# FTDI_ISP.net
KiCad netlist of a schematic drawn in Altium Designer
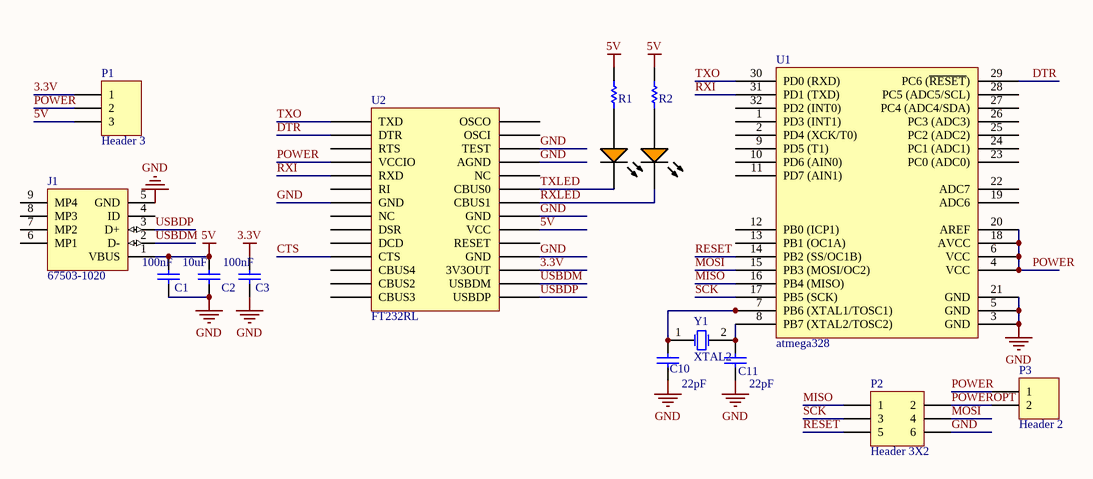
[diagram p0: FTDI_ISP.SchDoc]

(export (version "E")
  (design (tool "Eeschema 10.0.6"))
  (components
    (comp (ref "C1")
      (value "100nF")
      (footprint "CAPC0603(1608)100_N")
      (description "CAP 100nF 10V -20% to +80% 0603 (1608 Metric) Thickness 1mm SMD")
      (fields (field (name "TOLERANCE") "-20% to +80%"))
      (libsource (lib "Altium Content Vault") (part "CMP-1035-02582-1"))
    )
    (comp (ref "C2")
      (value "10uF")
      (footprint "CAPC0603(1608)100_N")
      (description "CAP 10uF 10V ±10% 0603 (1608 Metric) Thickness 1mm SMD")
      (fields (field (name "TOLERANCE") "±10%"))
      (libsource (lib "Altium Content Vault") (part "CMP-1035-02799-1"))
    )
    (comp (ref "C3")
      (value "100nF")
      (footprint "CAPC0603(1608)100_N")
      (description "CAP 100nF 10V -20% to +80% 0603 (1608 Metric) Thickness 1mm SMD")
      (fields (field (name "TOLERANCE") "-20% to +80%"))
      (libsource (lib "Altium Content Vault") (part "CMP-1035-02582-1"))
    )
    (comp (ref "C10")
      (value "22pF")
      (footprint "CAPC0603(1608)100_M")
      (description "CAP 22pF 10V ±0.25pF 0603 (1608 Metric) Thickness 1mm SMD")
      (fields (field (name "TOLERANCE") "±0.25pF"))
      (libsource (lib "Altium Content Vault") (part "CMP-1035-00797-1"))
    )
    (comp (ref "C11")
      (value "22pF")
      (footprint "CAPC0603(1608)100_M")
      (description "CAP 22pF 10V ±0.25pF 0603 (1608 Metric) Thickness 1mm SMD")
      (fields (field (name "TOLERANCE") "±0.25pF"))
      (libsource (lib "Altium Content Vault") (part "CMP-1035-00797-1"))
    )
    (comp (ref "D1")
      (value "APG1608SEKC/T")
      (footprint "KING-LED0603-25-ORANGE_V")
      (description "LED, SMT, 0603(1608), 0.25mm Tthickness, Super Bright Orange")
      (libsource (lib "Altium Content Vault") (part "CMP-0239-00002-1"))
    )
    (comp (ref "D2")
      (value "APG1608SEKC/T")
      (footprint "KING-LED0603-25-ORANGE_V")
      (description "LED, SMT, 0603(1608), 0.25mm Tthickness, Super Bright Orange")
      (libsource (lib "Altium Content Vault") (part "CMP-0239-00002-1"))
    )
    (comp (ref "J1")
      (value "67503-1020")
      (footprint "MOLX-67503-1020_V")
      (description "USB, MINI, SMD, RA KME04-USBMU03A01")
      (fields (field (name "MANUFACTURER") "Molex"))
      (libsource (lib "Altium Content Vault") (part "CMP-0411-00002-1"))
    )
    (comp (ref "P1")
      (value "Header 3")
      (footprint "HDR1X3")
      (description "Header, 3-Pin")
      (fields (field (name "PUBLISHER") "Altium Limited"))
      (libsource (lib "Miscellaneous Connectors") (part "Header 3"))
    )
    (comp (ref "P2")
      (value "Header 3X2")
      (footprint "HDR2X3")
      (description "Header, 3-Pin, Dual row")
      (fields (field (name "PUBLISHER") "Altium Limited"))
      (libsource (lib "Miscellaneous Connectors") (part "Header 3X2"))
    )
    (comp (ref "P3")
      (value "Header 2")
      (footprint "HDR1X2")
      (description "Header, 2-Pin")
      (fields (field (name "PUBLISHER") "Altium Limited"))
      (libsource (lib "Miscellaneous Connectors") (part "Header 2"))
    )
    (comp (ref "R1")
      (value "1K1 5% 0603(1608)")
      (footprint "RESC0603(1608)_N")
      (description "1K1 0.1W 5% 0603 (1608 Metric)  SMD")
      (fields (field (name "POWER") "0.1 W") (field (name "TOLERANCE") "5 %"))
      (libsource (lib "Altium Content Vault") (part "CMP-1012-00075-1"))
    )
    (comp (ref "R2")
      (value "1K1 5% 0603(1608)")
      (footprint "RESC0603(1608)_N")
      (description "1K1 0.1W 5% 0603 (1608 Metric)  SMD")
      (fields (field (name "POWER") "0.1 W") (field (name "TOLERANCE") "5 %"))
      (libsource (lib "Altium Content Vault") (part "CMP-1012-00075-1"))
    )
    (comp (ref "U1")
      (value "atmega328")
      (footprint "atmega44/88/168")
      (libsource (lib "Integrated_Library") (part "atmega88"))
    )
    (comp (ref "U2")
      (value "FT232RL")
      (footprint "FT232RL-SOP")
      (libsource (lib "Integrated_Library") (part "FT232RL"))
    )
    (comp (ref "Y1")
      (value "XTAL2")
      (footprint "HC49/US")
      (description "Two Lead Crystal Oscillator")
      (libsource (lib "Integrated_Library") (part "XTAL2"))
    )
  )
  (nets
    (net (code "1") (name "/CTS") (class "Default")
      (node (ref "U2") (pin "11") (pinfunction "CTS_11") (pintype "passive"))
    )
    (net (code "2") (name "/DTR") (class "Default")
      (node (ref "U1") (pin "29") (pinfunction "PC6_(~{RESET})_29") (pintype "passive"))
      (node (ref "U2") (pin "2") (pinfunction "DTR_2") (pintype "passive"))
    )
    (net (code "3") (name "/MISO") (class "Default")
      (node (ref "P2") (pin "1") (pinfunction "1_1") (pintype "passive"))
      (node (ref "U1") (pin "16") (pinfunction "PB4_(MISO)_16") (pintype "passive"))
    )
    (net (code "4") (name "/MOSI") (class "Default")
      (node (ref "P2") (pin "4") (pinfunction "4_4") (pintype "passive"))
      (node (ref "U1") (pin "15") (pinfunction "PB3_(MOSI/OC2)_15") (pintype "passive"))
    )
    (net (code "5") (name "/POWER") (class "Default")
      (node (ref "P1") (pin "2") (pinfunction "2_2") (pintype "passive"))
      (node (ref "P3") (pin "1") (pinfunction "1_1") (pintype "passive"))
      (node (ref "U1") (pin "18") (pinfunction "AVCC_18") (pintype "passive"))
      (node (ref "U1") (pin "20") (pinfunction "AREF_20") (pintype "passive"))
      (node (ref "U1") (pin "4") (pinfunction "VCC_4") (pintype "passive"))
      (node (ref "U1") (pin "6") (pinfunction "VCC_6") (pintype "passive"))
      (node (ref "U2") (pin "4") (pinfunction "VCCIO_4") (pintype "passive"))
    )
    (net (code "6") (name "/POWEROPT") (class "Default")
      (node (ref "P2") (pin "2") (pinfunction "2_2") (pintype "passive"))
      (node (ref "P3") (pin "2") (pinfunction "2_2") (pintype "passive"))
    )
    (net (code "7") (name "/RESET") (class "Default")
      (node (ref "P2") (pin "5") (pinfunction "5_5") (pintype "passive"))
      (node (ref "U1") (pin "14") (pinfunction "PB2_(SS/OC1B)_14") (pintype "passive"))
    )
    (net (code "8") (name "/RXI") (class "Default")
      (node (ref "U1") (pin "31") (pinfunction "PD1_(TXD)_31") (pintype "passive"))
      (node (ref "U2") (pin "5") (pinfunction "RXD_5") (pintype "passive"))
    )
    (net (code "9") (name "/RXLED") (class "Default")
      (node (ref "D2") (pin "2") (pinfunction "K_2") (pintype "passive"))
      (node (ref "U2") (pin "22") (pinfunction "CBUS1_22") (pintype "passive"))
    )
    (net (code "10") (name "/SCK") (class "Default")
      (node (ref "P2") (pin "3") (pinfunction "3_3") (pintype "passive"))
      (node (ref "U1") (pin "17") (pinfunction "PB5_(SCK)_17") (pintype "passive"))
    )
    (net (code "11") (name "/TXLED") (class "Default")
      (node (ref "D1") (pin "2") (pinfunction "K_2") (pintype "passive"))
      (node (ref "U2") (pin "23") (pinfunction "CBUS0_23") (pintype "passive"))
    )
    (net (code "12") (name "/TXO") (class "Default")
      (node (ref "U1") (pin "30") (pinfunction "PD0_(RXD)_30") (pintype "passive"))
      (node (ref "U2") (pin "1") (pinfunction "TXD_1") (pintype "passive"))
    )
    (net (code "13") (name "/USBDM") (class "Default")
      (node (ref "J1") (pin "2") (pinfunction "D-_2") (pintype "bidirectional"))
      (node (ref "U2") (pin "16") (pinfunction "USBDM_16") (pintype "passive"))
    )
    (net (code "14") (name "/USBDP") (class "Default")
      (node (ref "J1") (pin "3") (pinfunction "D+_3") (pintype "bidirectional"))
      (node (ref "U2") (pin "15") (pinfunction "USBDP_15") (pintype "passive"))
    )
    (net (code "15") (name "3.3V") (class "Default")
      (node (ref "C3") (pin "2") (pinfunction "2_2") (pintype "passive"))
      (node (ref "P1") (pin "1") (pinfunction "1_1") (pintype "passive"))
      (node (ref "U2") (pin "17") (pinfunction "3V3OUT_17") (pintype "passive"))
    )
    (net (code "16") (name "5V") (class "Default")
      (node (ref "C1") (pin "2") (pinfunction "2_2") (pintype "passive"))
      (node (ref "C2") (pin "2") (pinfunction "2_2") (pintype "passive"))
      (node (ref "J1") (pin "1") (pinfunction "VBUS_1") (pintype "power_in"))
      (node (ref "P1") (pin "3") (pinfunction "3_3") (pintype "passive"))
      (node (ref "R1") (pin "1") (pinfunction "1_1") (pintype "passive"))
      (node (ref "R2") (pin "1") (pinfunction "1_1") (pintype "passive"))
      (node (ref "U2") (pin "20") (pinfunction "VCC_20") (pintype "passive"))
    )
    (net (code "17") (name "GND") (class "Default")
      (node (ref "C1") (pin "1") (pinfunction "1_1") (pintype "passive"))
      (node (ref "C10") (pin "1") (pinfunction "1_1") (pintype "passive"))
      (node (ref "C11") (pin "1") (pinfunction "1_1") (pintype "passive"))
      (node (ref "C2") (pin "1") (pinfunction "1_1") (pintype "passive"))
      (node (ref "C3") (pin "1") (pinfunction "1_1") (pintype "passive"))
      (node (ref "J1") (pin "5") (pinfunction "GND_5") (pintype "power_in"))
      (node (ref "P2") (pin "6") (pinfunction "6_6") (pintype "passive"))
      (node (ref "U1") (pin "21") (pinfunction "GND_21") (pintype "passive"))
      (node (ref "U1") (pin "3") (pinfunction "GND_3") (pintype "passive"))
      (node (ref "U1") (pin "5") (pinfunction "GND_5") (pintype "passive"))
      (node (ref "U2") (pin "18") (pinfunction "GND_18") (pintype "passive"))
      (node (ref "U2") (pin "21") (pinfunction "GND_21") (pintype "passive"))
      (node (ref "U2") (pin "25") (pinfunction "AGND_25") (pintype "passive"))
      (node (ref "U2") (pin "26") (pinfunction "TEST_26") (pintype "passive"))
      (node (ref "U2") (pin "7") (pinfunction "GND_7") (pintype "passive"))
    )
    (net (code "18") (name "Net-(D1-A)") (class "Default")
      (node (ref "D1") (pin "1") (pinfunction "A_1") (pintype "passive"))
      (node (ref "R1") (pin "2") (pinfunction "2_2") (pintype "passive"))
    )
    (net (code "19") (name "Net-(D2-A)") (class "Default")
      (node (ref "D2") (pin "1") (pinfunction "A_1") (pintype "passive"))
      (node (ref "R2") (pin "2") (pinfunction "2_2") (pintype "passive"))
    )
    (net (code "20") (name "Net-(U1-PB6_(XTAL1{slash}TOSC1))") (class "Default")
      (node (ref "C10") (pin "2") (pinfunction "2_2") (pintype "passive"))
      (node (ref "U1") (pin "7") (pinfunction "PB6_(XTAL1/TOSC1)_7") (pintype "passive"))
      (node (ref "Y1") (pin "1") (pinfunction "OSC1_1") (pintype "passive"))
    )
    (net (code "21") (name "Net-(U1-PB7_(XTAL2{slash}TOSC2))") (class "Default")
      (node (ref "C11") (pin "2") (pinfunction "2_2") (pintype "passive"))
      (node (ref "U1") (pin "8") (pinfunction "PB7_(XTAL2/TOSC2)_8") (pintype "passive"))
      (node (ref "Y1") (pin "2") (pinfunction "OSC2_2") (pintype "passive"))
    )
    (net (code "22") (name "unconnected-(J1-ID-Pad4)") (class "Default")
      (node (ref "J1") (pin "4") (pinfunction "ID_4") (pintype "passive"))
    )
    (net (code "23") (name "unconnected-(J1-MP1-Pad6)") (class "Default")
      (node (ref "J1") (pin "6") (pinfunction "MP1_6") (pintype "passive"))
    )
    (net (code "24") (name "unconnected-(J1-MP2-Pad7)") (class "Default")
      (node (ref "J1") (pin "7") (pinfunction "MP2_7") (pintype "passive"))
    )
    (net (code "25") (name "unconnected-(J1-MP3-Pad8)") (class "Default")
      (node (ref "J1") (pin "8") (pinfunction "MP3_8") (pintype "passive"))
    )
    (net (code "26") (name "unconnected-(J1-MP4-Pad9)") (class "Default")
      (node (ref "J1") (pin "9") (pinfunction "MP4_9") (pintype "passive"))
    )
    (net (code "27") (name "unconnected-(U1-ADC6-Pad19)") (class "Default")
      (node (ref "U1") (pin "19") (pinfunction "ADC6_19") (pintype "passive"))
    )
    (net (code "28") (name "unconnected-(U1-ADC7-Pad22)") (class "Default")
      (node (ref "U1") (pin "22") (pinfunction "ADC7_22") (pintype "passive"))
    )
    (net (code "29") (name "unconnected-(U1-PB0_(ICP1)-Pad12)") (class "Default")
      (node (ref "U1") (pin "12") (pinfunction "PB0_(ICP1)_12") (pintype "passive"))
    )
    (net (code "30") (name "unconnected-(U1-PB1_(OC1A)-Pad13)") (class "Default")
      (node (ref "U1") (pin "13") (pinfunction "PB1_(OC1A)_13") (pintype "passive"))
    )
    (net (code "31") (name "unconnected-(U1-PC0_(ADC0)-Pad23)") (class "Default")
      (node (ref "U1") (pin "23") (pinfunction "PC0_(ADC0)_23") (pintype "passive"))
    )
    (net (code "32") (name "unconnected-(U1-PC1_(ADC1)-Pad24)") (class "Default")
      (node (ref "U1") (pin "24") (pinfunction "PC1_(ADC1)_24") (pintype "passive"))
    )
    (net (code "33") (name "unconnected-(U1-PC2_(ADC2)-Pad25)") (class "Default")
      (node (ref "U1") (pin "25") (pinfunction "PC2_(ADC2)_25") (pintype "passive"))
    )
    (net (code "34") (name "unconnected-(U1-PC3_(ADC3)-Pad26)") (class "Default")
      (node (ref "U1") (pin "26") (pinfunction "PC3_(ADC3)_26") (pintype "passive"))
    )
    (net (code "35") (name "unconnected-(U1-PC4_(ADC4{slash}SDA)-Pad27)") (class "Default")
      (node (ref "U1") (pin "27") (pinfunction "PC4_(ADC4/SDA)_27") (pintype "passive"))
    )
    (net (code "36") (name "unconnected-(U1-PC5_(ADC5{slash}SCL)-Pad28)") (class "Default")
      (node (ref "U1") (pin "28") (pinfunction "PC5_(ADC5/SCL)_28") (pintype "passive"))
    )
    (net (code "37") (name "unconnected-(U1-PD2_(INT0)-Pad32)") (class "Default")
      (node (ref "U1") (pin "32") (pinfunction "PD2_(INT0)_32") (pintype "passive"))
    )
    (net (code "38") (name "unconnected-(U1-PD3_(INT1)-Pad1)") (class "Default")
      (node (ref "U1") (pin "1") (pinfunction "PD3_(INT1)_1") (pintype "passive"))
    )
    (net (code "39") (name "unconnected-(U1-PD4_(XCK{slash}T0)-Pad2)") (class "Default")
      (node (ref "U1") (pin "2") (pinfunction "PD4_(XCK/T0)_2") (pintype "passive"))
    )
    (net (code "40") (name "unconnected-(U1-PD5_(T1)-Pad9)") (class "Default")
      (node (ref "U1") (pin "9") (pinfunction "PD5_(T1)_9") (pintype "passive"))
    )
    (net (code "41") (name "unconnected-(U1-PD6_(AIN0)-Pad10)") (class "Default")
      (node (ref "U1") (pin "10") (pinfunction "PD6_(AIN0)_10") (pintype "passive"))
    )
    (net (code "42") (name "unconnected-(U1-PD7_(AIN1)-Pad11)") (class "Default")
      (node (ref "U1") (pin "11") (pinfunction "PD7_(AIN1)_11") (pintype "passive"))
    )
    (net (code "43") (name "unconnected-(U2-CBUS2-Pad13)") (class "Default")
      (node (ref "U2") (pin "13") (pinfunction "CBUS2_13") (pintype "passive"))
    )
    (net (code "44") (name "unconnected-(U2-CBUS3-Pad14)") (class "Default")
      (node (ref "U2") (pin "14") (pinfunction "CBUS3_14") (pintype "passive"))
    )
    (net (code "45") (name "unconnected-(U2-CBUS4-Pad12)") (class "Default")
      (node (ref "U2") (pin "12") (pinfunction "CBUS4_12") (pintype "passive"))
    )
    (net (code "46") (name "unconnected-(U2-DCD-Pad10)") (class "Default")
      (node (ref "U2") (pin "10") (pinfunction "DCD_10") (pintype "passive"))
    )
    (net (code "47") (name "unconnected-(U2-DSR-Pad9)") (class "Default")
      (node (ref "U2") (pin "9") (pinfunction "DSR_9") (pintype "passive"))
    )
    (net (code "48") (name "unconnected-(U2-NC-Pad8)") (class "Default")
      (node (ref "U2") (pin "8") (pinfunction "NC_8") (pintype "passive"))
    )
    (net (code "49") (name "unconnected-(U2-NC-Pad24)") (class "Default")
      (node (ref "U2") (pin "24") (pinfunction "NC_24") (pintype "passive"))
    )
    (net (code "50") (name "unconnected-(U2-OSCI-Pad27)") (class "Default")
      (node (ref "U2") (pin "27") (pinfunction "OSCI_27") (pintype "passive"))
    )
    (net (code "51") (name "unconnected-(U2-OSCO-Pad28)") (class "Default")
      (node (ref "U2") (pin "28") (pinfunction "OSCO_28") (pintype "passive"))
    )
    (net (code "52") (name "unconnected-(U2-RESET-Pad19)") (class "Default")
      (node (ref "U2") (pin "19") (pinfunction "RESET_19") (pintype "passive"))
    )
    (net (code "53") (name "unconnected-(U2-RI-Pad6)") (class "Default")
      (node (ref "U2") (pin "6") (pinfunction "RI_6") (pintype "passive"))
    )
    (net (code "54") (name "unconnected-(U2-RTS-Pad3)") (class "Default")
      (node (ref "U2") (pin "3") (pinfunction "RTS_3") (pintype "passive"))
    )
  )
)
